# OC_Trigger.net
KiCad netlist of a schematic drawn in Altium Designer
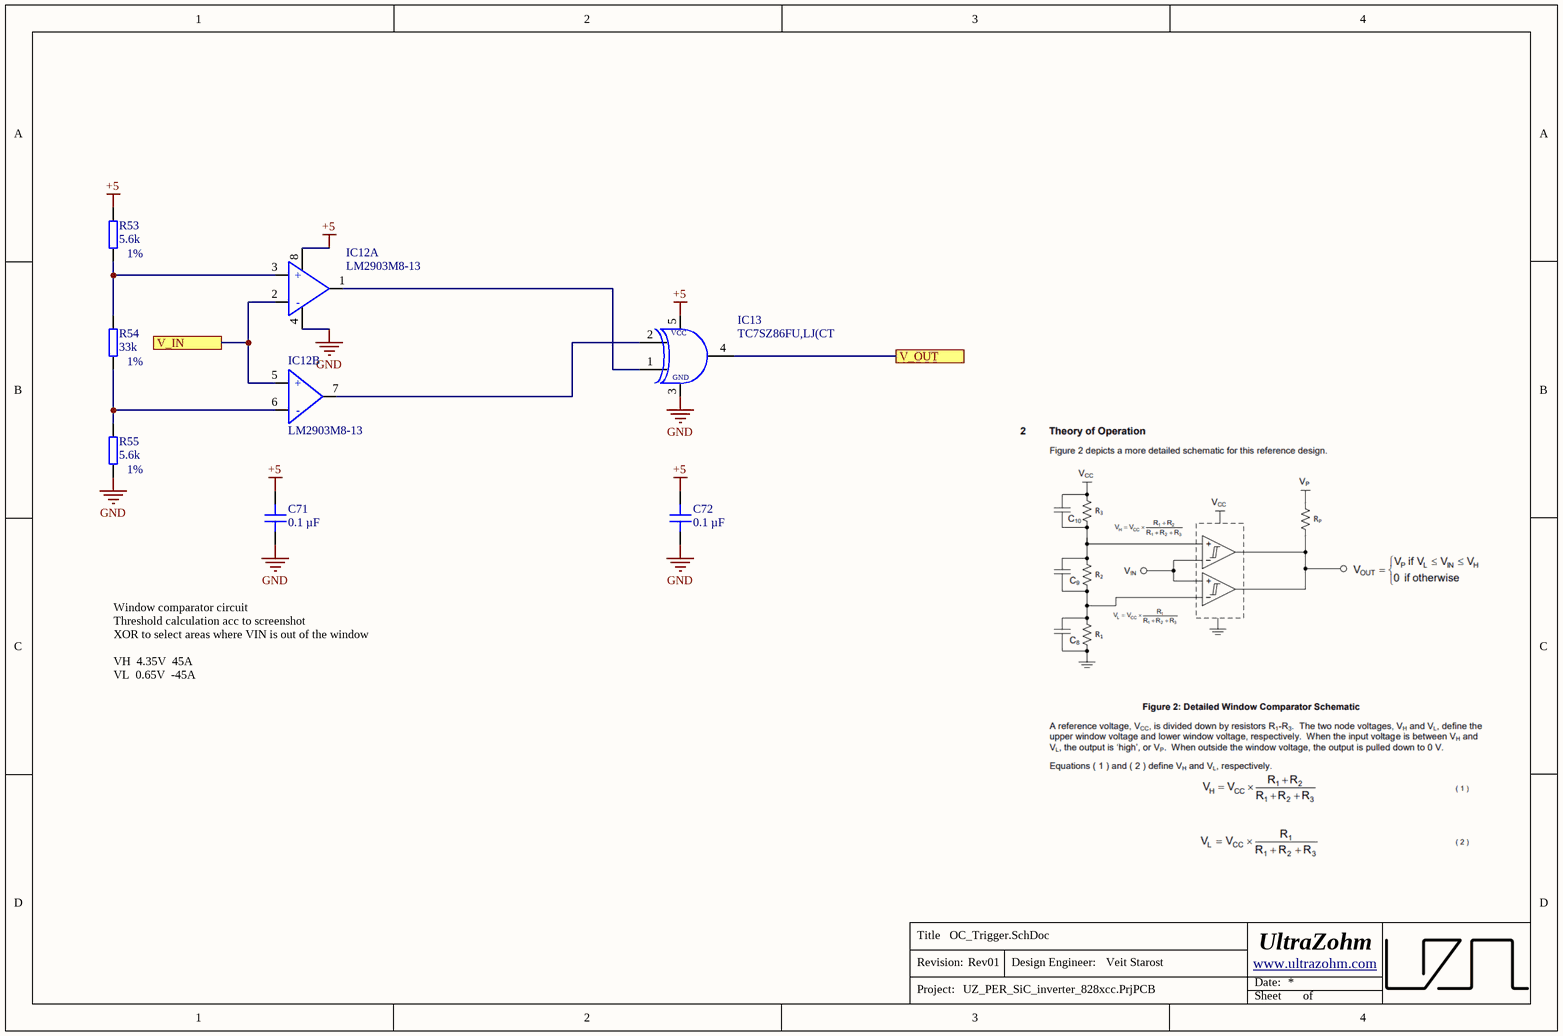
[diagram p0: OC_Trigger.SchDoc]

(export (version "E")
  (design (tool "Eeschema 10.0.6"))
  (components
    (comp (ref "C71")
      (value "0.1 µF")
      (footprint "C_0603")
      (description "Capacitor 0603, 50 VDC, 0.1 µF, X7R")
      (fields
        (field (name "MANUFACTURER PART NUMBER") "C0603X104K5RAC7411")
        (field (name "MANUFACTURER") "KEMET")
        (field (name "CREATED FROM") "MGremer")
      )
      (libsource (lib "user") (part "Capacitor"))
    )
    (comp (ref "C72")
      (value "0.1 µF")
      (footprint "C_0603")
      (description "Capacitor 0603, 50 VDC, 0.1 µF, X7R")
      (fields
        (field (name "MANUFACTURER PART NUMBER") "C0603X104K5RAC7411")
        (field (name "MANUFACTURER") "KEMET")
        (field (name "CREATED FROM") "MGremer")
      )
      (libsource (lib "user") (part "Capacitor"))
    )
    (comp (ref "IC12")
      (value "LM2903M8-13")
      (footprint "MSOP-8 (RM-8)")
      (description "Analoge Komparatoren Comparator")
      (fields (field (name "MANUFACTURER") "Diodes Incorporated") (field (name "CREATED FROM") "VStarost"))
      (libsource (lib "user") (part "LM358DR"))
    )
    (comp (ref "IC13")
      (value "TC7SZ86FU,LJ(CT")
      (footprint "SOT353-1_N")
      (description "IC GATE XOR 1CH 2-INP USV")
      (fields (field (name "MANUFACTURER") "Toshiba") (field (name "CREATED FROM") "VStarost"))
      (libsource (lib "user") (part "XOR"))
    )
    (comp (ref "R53")
      (value "5.6k")
      (footprint "RES 0603_1608")
      (description "SMD resistor E24 series 5.6 kOhms 100mW 0603 1%")
      (fields
        (field (name "MANUFACTURER PART NUMBER") "AC0603FR-075K6L")
        (field (name "MANUFACTURER") "YAGEO")
        (field (name "TOLERANCE") "1%")
        (field (name "CREATED FROM") "VStarost")
      )
      (libsource (lib "user") (part "Resistor"))
    )
    (comp (ref "R54")
      (value "33k")
      (footprint "RES 0603_1608")
      (description "SMD resistor E24 series")
      (fields
        (field (name "MANUFACTURER PART NUMBER") "AC0603FR-1333KL")
        (field (name "MANUFACTURER") "YAGEO")
        (field (name "TOLERANCE") "1%")
        (field (name "CREATED FROM") "VStarost")
      )
      (libsource (lib "user") (part "Resistor"))
    )
    (comp (ref "R55")
      (value "5.6k")
      (footprint "RES 0603_1608")
      (description "SMD resistor E24 series 5.6 kOhms 100mW 0603 1%")
      (fields
        (field (name "MANUFACTURER PART NUMBER") "AC0603FR-075K6L")
        (field (name "MANUFACTURER") "YAGEO")
        (field (name "TOLERANCE") "1%")
        (field (name "CREATED FROM") "VStarost")
      )
      (libsource (lib "user") (part "Resistor"))
    )
  )
  (nets
    (net (code "1") (name "+5") (class "Default")
      (node (ref "C71") (pin "2") (pinfunction "2_2") (pintype "passive"))
      (node (ref "C72") (pin "2") (pinfunction "2_2") (pintype "passive"))
      (node (ref "IC12") (pin "8") (pintype "passive"))
      (node (ref "IC13") (pin "5") (pinfunction "5_5") (pintype "passive"))
      (node (ref "R53") (pin "2") (pinfunction "2_2") (pintype "passive"))
    )
    (net (code "2") (name "/V_IN") (class "Default")
      (node (ref "IC12") (pin "2") (pinfunction "-_2") (pintype "passive"))
      (node (ref "IC12") (pin "5") (pinfunction "+_5") (pintype "passive"))
    )
    (net (code "3") (name "/V_OUT") (class "Default")
      (node (ref "IC13") (pin "4") (pinfunction "4_4") (pintype "passive"))
    )
    (net (code "4") (name "GND") (class "Default")
      (node (ref "C71") (pin "1") (pinfunction "1_1") (pintype "passive"))
      (node (ref "C72") (pin "1") (pinfunction "1_1") (pintype "passive"))
      (node (ref "IC12") (pin "4") (pintype "passive"))
      (node (ref "IC13") (pin "3") (pinfunction "3_3") (pintype "passive"))
      (node (ref "R55") (pin "1") (pinfunction "1_1") (pintype "passive"))
    )
    (net (code "5") (name "Net-(IC12-Pad1)") (class "Default")
      (node (ref "IC12") (pin "1") (pintype "passive"))
      (node (ref "IC13") (pin "1") (pinfunction "1_1") (pintype "passive"))
    )
    (net (code "6") (name "Net-(IC12-Pad7)") (class "Default")
      (node (ref "IC12") (pin "7") (pintype "passive"))
      (node (ref "IC13") (pin "2") (pinfunction "2_2") (pintype "passive"))
    )
    (net (code "7") (name "Net-(IC12A-+)") (class "Default")
      (node (ref "IC12") (pin "3") (pinfunction "+_3") (pintype "passive"))
      (node (ref "R53") (pin "1") (pinfunction "1_1") (pintype "passive"))
      (node (ref "R54") (pin "2") (pinfunction "2_2") (pintype "passive"))
    )
    (net (code "8") (name "Net-(IC12B--)") (class "Default")
      (node (ref "IC12") (pin "6") (pinfunction "-_6") (pintype "passive"))
      (node (ref "R54") (pin "1") (pinfunction "1_1") (pintype "passive"))
      (node (ref "R55") (pin "2") (pinfunction "2_2") (pintype "passive"))
    )
  )
)
